# Famicom_Controller.net
KiCad netlist of a schematic drawn in EAGLE
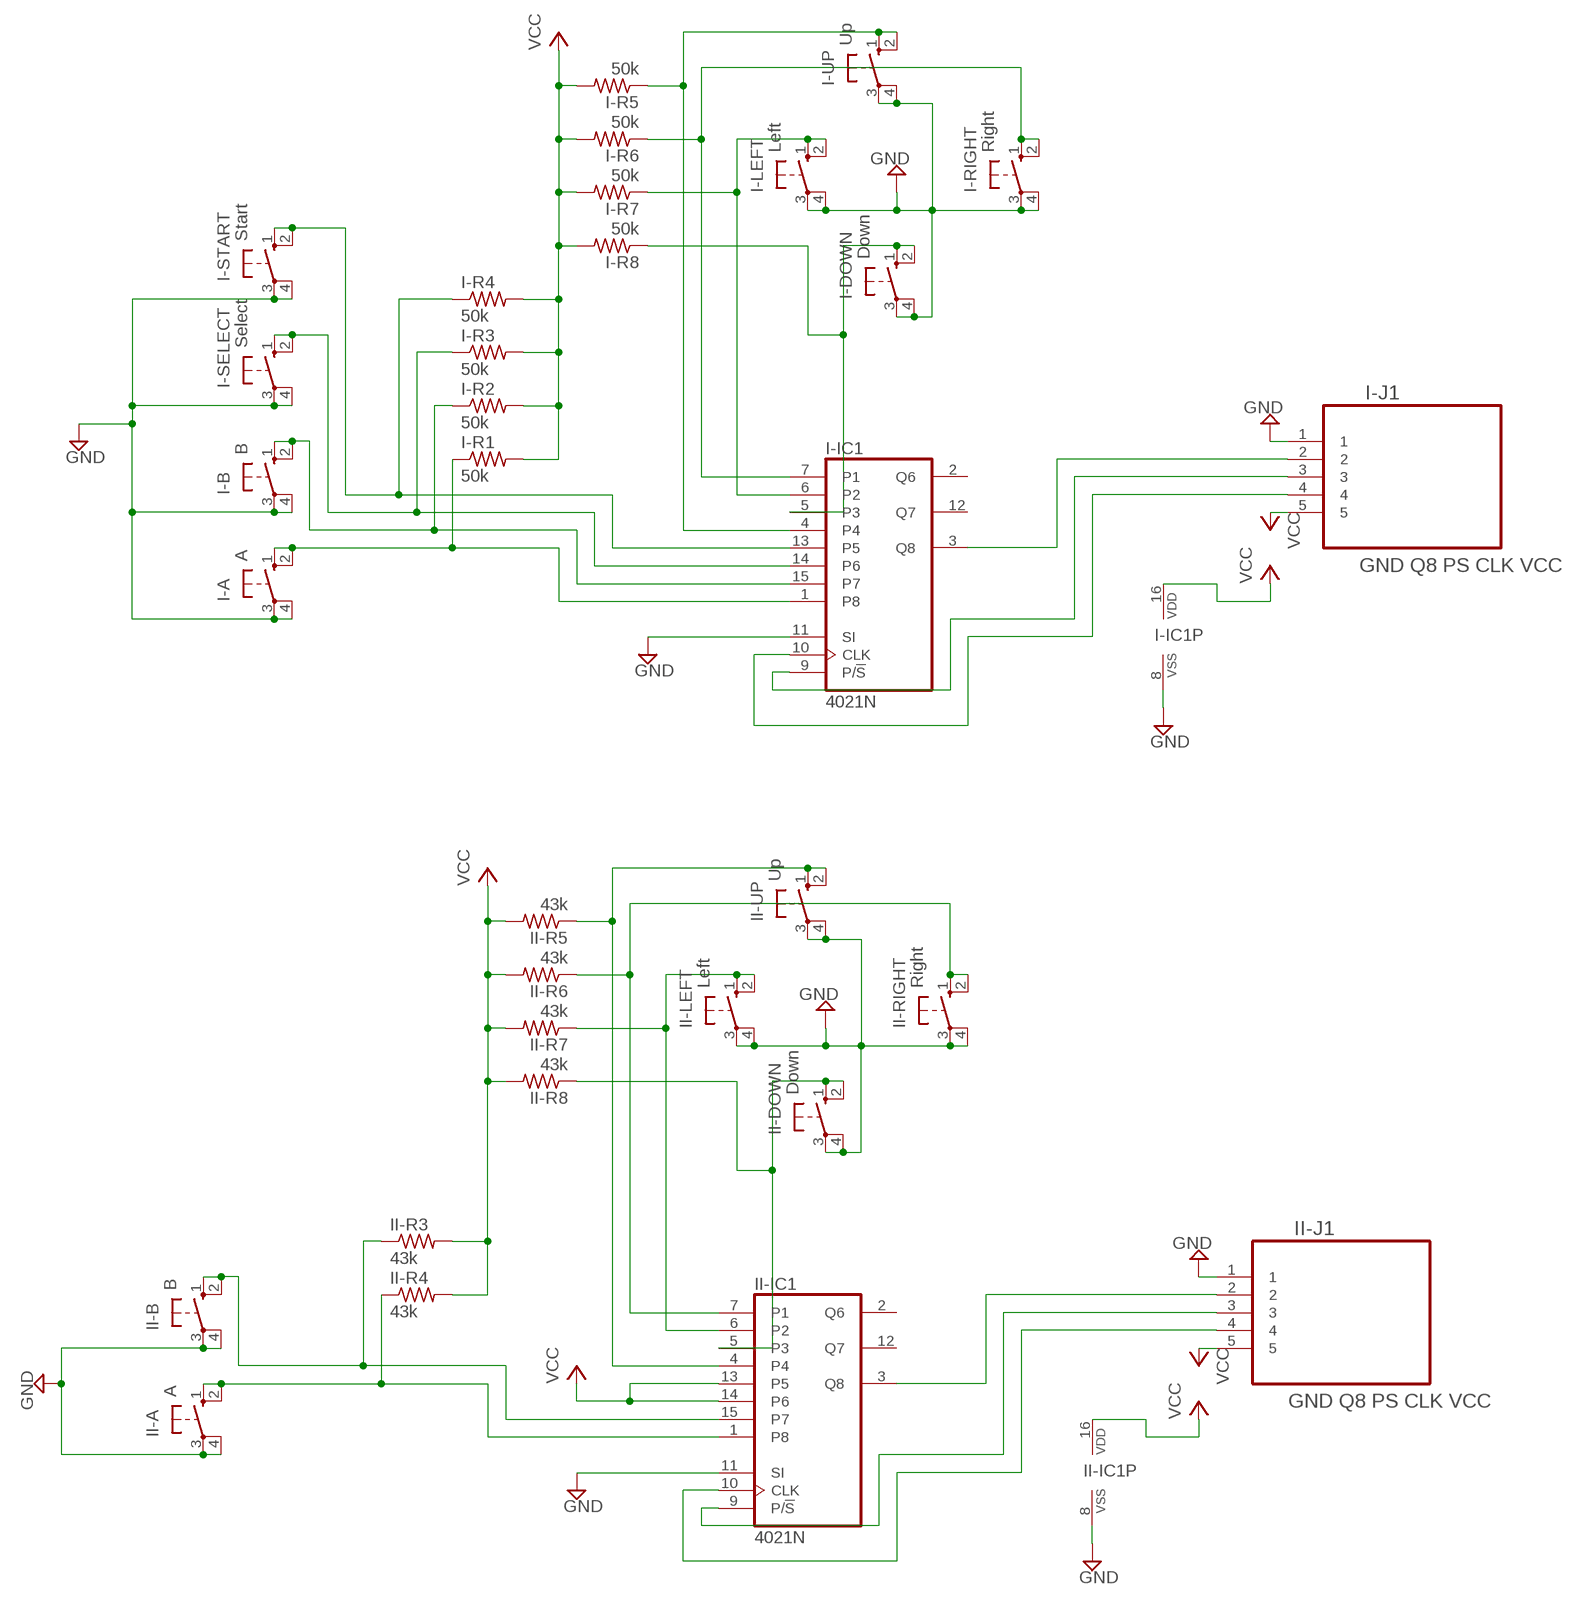
[diagram p0: schematic, sheet 1]

(export (version "E")
  (design (tool "Eeschema 10.0.6"))
  (components
    (comp (ref "I-A")
      (value "A")
      (footprint "eagle-import:B3F-10XX")
      (fields (field (name "MPN") "B3F-1000"))
      (libsource (lib "eagle-import") (part "10-XX"))
    )
    (comp (ref "I-B")
      (value "B")
      (footprint "eagle-import:B3F-10XX")
      (fields (field (name "MPN") "B3F-1000"))
      (libsource (lib "eagle-import") (part "10-XX"))
    )
    (comp (ref "I-DOWN")
      (value "Down")
      (footprint "eagle-import:B3F-10XX")
      (fields (field (name "MPN") "B3F-1000"))
      (libsource (lib "eagle-import") (part "10-XX"))
    )
    (comp (ref "I-IC1")
      (value "4021N")
      (footprint "eagle-import:DIL16")
      (libsource (lib "eagle-import") (part "4021N"))
    )
    (comp (ref "I-J1")
      (value "GND Q8 PS CLK VCC")
      (footprint "eagle-import:SAMTEC_TLW-105-05-G-S")
      (fields (field (name "MPN") "TLW-105-05-G-S"))
      (libsource (lib "eagle-import") (part "TLW-105-05-G-S"))
    )
    (comp (ref "I-LEFT")
      (value "Left")
      (footprint "eagle-import:B3F-10XX")
      (fields (field (name "MPN") "B3F-1000"))
      (libsource (lib "eagle-import") (part "10-XX"))
    )
    (comp (ref "I-R1")
      (value "50k")
      (footprint "eagle-import:0207_7")
      (libsource (lib "eagle-import") (part "R-US_0207/7"))
    )
    (comp (ref "I-R2")
      (value "50k")
      (footprint "eagle-import:0207_7")
      (libsource (lib "eagle-import") (part "R-US_0207/7"))
    )
    (comp (ref "I-R3")
      (value "50k")
      (footprint "eagle-import:0207_7")
      (libsource (lib "eagle-import") (part "R-US_0207/7"))
    )
    (comp (ref "I-R4")
      (value "50k")
      (footprint "eagle-import:0207_7")
      (libsource (lib "eagle-import") (part "R-US_0207/7"))
    )
    (comp (ref "I-R5")
      (value "50k")
      (footprint "eagle-import:0207_7")
      (libsource (lib "eagle-import") (part "R-US_0207/7"))
    )
    (comp (ref "I-R6")
      (value "50k")
      (footprint "eagle-import:0207_7")
      (libsource (lib "eagle-import") (part "R-US_0207/7"))
    )
    (comp (ref "I-R7")
      (value "50k")
      (footprint "eagle-import:0207_7")
      (libsource (lib "eagle-import") (part "R-US_0207/7"))
    )
    (comp (ref "I-R8")
      (value "50k")
      (footprint "eagle-import:0207_7")
      (libsource (lib "eagle-import") (part "R-US_0207/7"))
    )
    (comp (ref "I-RIGHT")
      (value "Right")
      (footprint "eagle-import:B3F-10XX")
      (fields (field (name "MPN") "B3F-1000"))
      (libsource (lib "eagle-import") (part "10-XX"))
    )
    (comp (ref "I-SELECT")
      (value "Select")
      (footprint "eagle-import:B3F-10XX")
      (fields (field (name "MPN") "B3F-1000"))
      (libsource (lib "eagle-import") (part "10-XX"))
    )
    (comp (ref "I-START")
      (value "Start")
      (footprint "eagle-import:B3F-10XX")
      (fields (field (name "MPN") "B3F-1000"))
      (libsource (lib "eagle-import") (part "10-XX"))
    )
    (comp (ref "I-UP")
      (value "Up")
      (footprint "eagle-import:B3F-10XX")
      (fields (field (name "MPN") "B3F-1000"))
      (libsource (lib "eagle-import") (part "10-XX"))
    )
    (comp (ref "II-A")
      (value "A")
      (footprint "eagle-import:B3F-10XX")
      (fields (field (name "MPN") "B3F-1000"))
      (libsource (lib "eagle-import") (part "10-XX"))
    )
    (comp (ref "II-B")
      (value "B")
      (footprint "eagle-import:B3F-10XX")
      (fields (field (name "MPN") "B3F-1000"))
      (libsource (lib "eagle-import") (part "10-XX"))
    )
    (comp (ref "II-DOWN")
      (value "Down")
      (footprint "eagle-import:B3F-10XX")
      (fields (field (name "MPN") "B3F-1000"))
      (libsource (lib "eagle-import") (part "10-XX"))
    )
    (comp (ref "II-IC1")
      (value "4021N")
      (footprint "eagle-import:DIL16")
      (libsource (lib "eagle-import") (part "4021N"))
    )
    (comp (ref "II-J1")
      (value "GND Q8 PS CLK VCC")
      (footprint "eagle-import:SAMTEC_TLW-105-05-G-S")
      (fields (field (name "MPN") "TLW-105-05-G-S"))
      (libsource (lib "eagle-import") (part "TLW-105-05-G-S"))
    )
    (comp (ref "II-LEFT")
      (value "Left")
      (footprint "eagle-import:B3F-10XX")
      (fields (field (name "MPN") "B3F-1000"))
      (libsource (lib "eagle-import") (part "10-XX"))
    )
    (comp (ref "II-R3")
      (value "43k")
      (footprint "eagle-import:0207_7")
      (libsource (lib "eagle-import") (part "R-US_0207/7"))
    )
    (comp (ref "II-R4")
      (value "43k")
      (footprint "eagle-import:0207_7")
      (libsource (lib "eagle-import") (part "R-US_0207/7"))
    )
    (comp (ref "II-R5")
      (value "43k")
      (footprint "eagle-import:0207_7")
      (libsource (lib "eagle-import") (part "R-US_0207/7"))
    )
    (comp (ref "II-R6")
      (value "43k")
      (footprint "eagle-import:0207_7")
      (libsource (lib "eagle-import") (part "R-US_0207/7"))
    )
    (comp (ref "II-R7")
      (value "43k")
      (footprint "eagle-import:0207_7")
      (libsource (lib "eagle-import") (part "R-US_0207/7"))
    )
    (comp (ref "II-R8")
      (value "43k")
      (footprint "eagle-import:0207_7")
      (libsource (lib "eagle-import") (part "R-US_0207/7"))
    )
    (comp (ref "II-RIGHT")
      (value "Right")
      (footprint "eagle-import:B3F-10XX")
      (fields (field (name "MPN") "B3F-1000"))
      (libsource (lib "eagle-import") (part "10-XX"))
    )
    (comp (ref "II-UP")
      (value "Up")
      (footprint "eagle-import:B3F-10XX")
      (fields (field (name "MPN") "B3F-1000"))
      (libsource (lib "eagle-import") (part "10-XX"))
    )
  )
  (nets
    (net (code "1") (name "GND") (class "Default")
      (node (ref "I-A") (pin "3") (pinfunction "P_3") (pintype "passive"))
      (node (ref "I-A") (pin "4") (pinfunction "P1_4") (pintype "passive"))
      (node (ref "I-B") (pin "3") (pinfunction "P_3") (pintype "passive"))
      (node (ref "I-B") (pin "4") (pinfunction "P1_4") (pintype "passive"))
      (node (ref "I-DOWN") (pin "3") (pinfunction "P_3") (pintype "passive"))
      (node (ref "I-DOWN") (pin "4") (pinfunction "P1_4") (pintype "passive"))
      (node (ref "I-IC1") (pin "11") (pinfunction "SI_11") (pintype "input"))
      (node (ref "I-IC1") (pin "8") (pinfunction "VSS_8") (pintype "power_in"))
      (node (ref "I-J1") (pin "1") (pinfunction "1_1") (pintype "passive"))
      (node (ref "I-LEFT") (pin "3") (pinfunction "P_3") (pintype "passive"))
      (node (ref "I-LEFT") (pin "4") (pinfunction "P1_4") (pintype "passive"))
      (node (ref "I-RIGHT") (pin "3") (pinfunction "P_3") (pintype "passive"))
      (node (ref "I-RIGHT") (pin "4") (pinfunction "P1_4") (pintype "passive"))
      (node (ref "I-SELECT") (pin "3") (pinfunction "P_3") (pintype "passive"))
      (node (ref "I-SELECT") (pin "4") (pinfunction "P1_4") (pintype "passive"))
      (node (ref "I-START") (pin "3") (pinfunction "P_3") (pintype "passive"))
      (node (ref "I-START") (pin "4") (pinfunction "P1_4") (pintype "passive"))
      (node (ref "I-UP") (pin "3") (pinfunction "P_3") (pintype "passive"))
      (node (ref "I-UP") (pin "4") (pinfunction "P1_4") (pintype "passive"))
      (node (ref "II-A") (pin "3") (pinfunction "P_3") (pintype "passive"))
      (node (ref "II-A") (pin "4") (pinfunction "P1_4") (pintype "passive"))
      (node (ref "II-B") (pin "3") (pinfunction "P_3") (pintype "passive"))
      (node (ref "II-B") (pin "4") (pinfunction "P1_4") (pintype "passive"))
      (node (ref "II-DOWN") (pin "3") (pinfunction "P_3") (pintype "passive"))
      (node (ref "II-DOWN") (pin "4") (pinfunction "P1_4") (pintype "passive"))
      (node (ref "II-IC1") (pin "11") (pinfunction "SI_11") (pintype "input"))
      (node (ref "II-IC1") (pin "8") (pinfunction "VSS_8") (pintype "power_in"))
      (node (ref "II-J1") (pin "1") (pinfunction "1_1") (pintype "passive"))
      (node (ref "II-LEFT") (pin "3") (pinfunction "P_3") (pintype "passive"))
      (node (ref "II-LEFT") (pin "4") (pinfunction "P1_4") (pintype "passive"))
      (node (ref "II-RIGHT") (pin "3") (pinfunction "P_3") (pintype "passive"))
      (node (ref "II-RIGHT") (pin "4") (pinfunction "P1_4") (pintype "passive"))
      (node (ref "II-UP") (pin "3") (pinfunction "P_3") (pintype "passive"))
      (node (ref "II-UP") (pin "4") (pinfunction "P1_4") (pintype "passive"))
    )
    (net (code "2") (name "Net-(I-A-S)") (class "Default")
      (node (ref "I-A") (pin "1") (pinfunction "S_1") (pintype "passive"))
      (node (ref "I-A") (pin "2") (pinfunction "S1_2") (pintype "passive"))
      (node (ref "I-IC1") (pin "1") (pinfunction "P8_1") (pintype "input"))
      (node (ref "I-R1") (pin "1") (pinfunction "1_1") (pintype "passive"))
    )
    (net (code "3") (name "Net-(I-B-S)") (class "Default")
      (node (ref "I-B") (pin "1") (pinfunction "S_1") (pintype "passive"))
      (node (ref "I-B") (pin "2") (pinfunction "S1_2") (pintype "passive"))
      (node (ref "I-IC1") (pin "15") (pinfunction "P7_15") (pintype "input"))
      (node (ref "I-R2") (pin "1") (pinfunction "1_1") (pintype "passive"))
    )
    (net (code "4") (name "Net-(I-DOWN-S)") (class "Default")
      (node (ref "I-DOWN") (pin "1") (pinfunction "S_1") (pintype "passive"))
      (node (ref "I-DOWN") (pin "2") (pinfunction "S1_2") (pintype "passive"))
      (node (ref "I-IC1") (pin "5") (pinfunction "P3_5") (pintype "input"))
      (node (ref "I-R8") (pin "1") (pinfunction "1_1") (pintype "passive"))
    )
    (net (code "5") (name "Net-(I-IC1A-CLK)") (class "Default")
      (node (ref "I-IC1") (pin "10") (pinfunction "CLK_10") (pintype "input"))
      (node (ref "I-J1") (pin "4") (pinfunction "4_4") (pintype "passive"))
    )
    (net (code "6") (name "Net-(I-IC1A-P1)") (class "Default")
      (node (ref "I-IC1") (pin "7") (pinfunction "P1_7") (pintype "input"))
      (node (ref "I-R6") (pin "1") (pinfunction "1_1") (pintype "passive"))
      (node (ref "I-RIGHT") (pin "1") (pinfunction "S_1") (pintype "passive"))
      (node (ref "I-RIGHT") (pin "2") (pinfunction "S1_2") (pintype "passive"))
    )
    (net (code "7") (name "Net-(I-IC1A-P2)") (class "Default")
      (node (ref "I-IC1") (pin "6") (pinfunction "P2_6") (pintype "input"))
      (node (ref "I-LEFT") (pin "1") (pinfunction "S_1") (pintype "passive"))
      (node (ref "I-LEFT") (pin "2") (pinfunction "S1_2") (pintype "passive"))
      (node (ref "I-R7") (pin "1") (pinfunction "1_1") (pintype "passive"))
    )
    (net (code "8") (name "Net-(I-IC1A-P4)") (class "Default")
      (node (ref "I-IC1") (pin "4") (pinfunction "P4_4") (pintype "input"))
      (node (ref "I-R5") (pin "1") (pinfunction "1_1") (pintype "passive"))
      (node (ref "I-UP") (pin "1") (pinfunction "S_1") (pintype "passive"))
      (node (ref "I-UP") (pin "2") (pinfunction "S1_2") (pintype "passive"))
    )
    (net (code "9") (name "Net-(I-IC1A-P5)") (class "Default")
      (node (ref "I-IC1") (pin "13") (pinfunction "P5_13") (pintype "input"))
      (node (ref "I-R4") (pin "1") (pinfunction "1_1") (pintype "passive"))
      (node (ref "I-START") (pin "1") (pinfunction "S_1") (pintype "passive"))
      (node (ref "I-START") (pin "2") (pinfunction "S1_2") (pintype "passive"))
    )
    (net (code "10") (name "Net-(I-IC1A-P6)") (class "Default")
      (node (ref "I-IC1") (pin "14") (pinfunction "P6_14") (pintype "input"))
      (node (ref "I-R3") (pin "1") (pinfunction "1_1") (pintype "passive"))
      (node (ref "I-SELECT") (pin "1") (pinfunction "S_1") (pintype "passive"))
      (node (ref "I-SELECT") (pin "2") (pinfunction "S1_2") (pintype "passive"))
    )
    (net (code "11") (name "Net-(I-IC1A-P{slash}~{S})") (class "Default")
      (node (ref "I-IC1") (pin "9") (pinfunction "P/~{S}_9") (pintype "input"))
      (node (ref "I-J1") (pin "3") (pinfunction "3_3") (pintype "passive"))
    )
    (net (code "12") (name "Net-(I-IC1A-Q8)") (class "Default")
      (node (ref "I-IC1") (pin "3") (pinfunction "Q8_3") (pintype "output"))
      (node (ref "I-J1") (pin "2") (pinfunction "2_2") (pintype "passive"))
    )
    (net (code "13") (name "Net-(II-A-S)") (class "Default")
      (node (ref "II-A") (pin "1") (pinfunction "S_1") (pintype "passive"))
      (node (ref "II-A") (pin "2") (pinfunction "S1_2") (pintype "passive"))
      (node (ref "II-IC1") (pin "1") (pinfunction "P8_1") (pintype "input"))
      (node (ref "II-R4") (pin "1") (pinfunction "1_1") (pintype "passive"))
    )
    (net (code "14") (name "Net-(II-B-S)") (class "Default")
      (node (ref "II-B") (pin "1") (pinfunction "S_1") (pintype "passive"))
      (node (ref "II-B") (pin "2") (pinfunction "S1_2") (pintype "passive"))
      (node (ref "II-IC1") (pin "15") (pinfunction "P7_15") (pintype "input"))
      (node (ref "II-R3") (pin "1") (pinfunction "1_1") (pintype "passive"))
    )
    (net (code "15") (name "Net-(II-DOWN-S)") (class "Default")
      (node (ref "II-DOWN") (pin "1") (pinfunction "S_1") (pintype "passive"))
      (node (ref "II-DOWN") (pin "2") (pinfunction "S1_2") (pintype "passive"))
      (node (ref "II-IC1") (pin "5") (pinfunction "P3_5") (pintype "input"))
      (node (ref "II-R8") (pin "1") (pinfunction "1_1") (pintype "passive"))
    )
    (net (code "16") (name "Net-(II-IC1A-CLK)") (class "Default")
      (node (ref "II-IC1") (pin "10") (pinfunction "CLK_10") (pintype "input"))
      (node (ref "II-J1") (pin "4") (pinfunction "4_4") (pintype "passive"))
    )
    (net (code "17") (name "Net-(II-IC1A-P1)") (class "Default")
      (node (ref "II-IC1") (pin "7") (pinfunction "P1_7") (pintype "input"))
      (node (ref "II-R6") (pin "1") (pinfunction "1_1") (pintype "passive"))
      (node (ref "II-RIGHT") (pin "1") (pinfunction "S_1") (pintype "passive"))
      (node (ref "II-RIGHT") (pin "2") (pinfunction "S1_2") (pintype "passive"))
    )
    (net (code "18") (name "Net-(II-IC1A-P2)") (class "Default")
      (node (ref "II-IC1") (pin "6") (pinfunction "P2_6") (pintype "input"))
      (node (ref "II-LEFT") (pin "1") (pinfunction "S_1") (pintype "passive"))
      (node (ref "II-LEFT") (pin "2") (pinfunction "S1_2") (pintype "passive"))
      (node (ref "II-R7") (pin "1") (pinfunction "1_1") (pintype "passive"))
    )
    (net (code "19") (name "Net-(II-IC1A-P4)") (class "Default")
      (node (ref "II-IC1") (pin "4") (pinfunction "P4_4") (pintype "input"))
      (node (ref "II-R5") (pin "1") (pinfunction "1_1") (pintype "passive"))
      (node (ref "II-UP") (pin "1") (pinfunction "S_1") (pintype "passive"))
      (node (ref "II-UP") (pin "2") (pinfunction "S1_2") (pintype "passive"))
    )
    (net (code "20") (name "Net-(II-IC1A-P{slash}~{S})") (class "Default")
      (node (ref "II-IC1") (pin "9") (pinfunction "P/~{S}_9") (pintype "input"))
      (node (ref "II-J1") (pin "3") (pinfunction "3_3") (pintype "passive"))
    )
    (net (code "21") (name "Net-(II-IC1A-Q8)") (class "Default")
      (node (ref "II-IC1") (pin "3") (pinfunction "Q8_3") (pintype "output"))
      (node (ref "II-J1") (pin "2") (pinfunction "2_2") (pintype "passive"))
    )
    (net (code "22") (name "VCC") (class "Default")
      (node (ref "I-IC1") (pin "16") (pinfunction "VDD_16") (pintype "power_in"))
      (node (ref "I-J1") (pin "5") (pinfunction "5_5") (pintype "passive"))
      (node (ref "I-R1") (pin "2") (pinfunction "2_2") (pintype "passive"))
      (node (ref "I-R2") (pin "2") (pinfunction "2_2") (pintype "passive"))
      (node (ref "I-R3") (pin "2") (pinfunction "2_2") (pintype "passive"))
      (node (ref "I-R4") (pin "2") (pinfunction "2_2") (pintype "passive"))
      (node (ref "I-R5") (pin "2") (pinfunction "2_2") (pintype "passive"))
      (node (ref "I-R6") (pin "2") (pinfunction "2_2") (pintype "passive"))
      (node (ref "I-R7") (pin "2") (pinfunction "2_2") (pintype "passive"))
      (node (ref "I-R8") (pin "2") (pinfunction "2_2") (pintype "passive"))
      (node (ref "II-IC1") (pin "13") (pinfunction "P5_13") (pintype "input"))
      (node (ref "II-IC1") (pin "14") (pinfunction "P6_14") (pintype "input"))
      (node (ref "II-IC1") (pin "16") (pinfunction "VDD_16") (pintype "power_in"))
      (node (ref "II-J1") (pin "5") (pinfunction "5_5") (pintype "passive"))
      (node (ref "II-R3") (pin "2") (pinfunction "2_2") (pintype "passive"))
      (node (ref "II-R4") (pin "2") (pinfunction "2_2") (pintype "passive"))
      (node (ref "II-R5") (pin "2") (pinfunction "2_2") (pintype "passive"))
      (node (ref "II-R6") (pin "2") (pinfunction "2_2") (pintype "passive"))
      (node (ref "II-R7") (pin "2") (pinfunction "2_2") (pintype "passive"))
      (node (ref "II-R8") (pin "2") (pinfunction "2_2") (pintype "passive"))
    )
    (net (code "23") (name "unconnected-(I-IC1A-Q6-Pad2)") (class "Default")
      (node (ref "I-IC1") (pin "2") (pinfunction "Q6_2") (pintype "output"))
    )
    (net (code "24") (name "unconnected-(I-IC1A-Q7-Pad12)") (class "Default")
      (node (ref "I-IC1") (pin "12") (pinfunction "Q7_12") (pintype "output"))
    )
    (net (code "25") (name "unconnected-(II-IC1A-Q6-Pad2)") (class "Default")
      (node (ref "II-IC1") (pin "2") (pinfunction "Q6_2") (pintype "output"))
    )
    (net (code "26") (name "unconnected-(II-IC1A-Q7-Pad12)") (class "Default")
      (node (ref "II-IC1") (pin "12") (pinfunction "Q7_12") (pintype "output"))
    )
  )
)
